# tm-duplicator.net
KiCad netlist of a schematic drawn in EasyEDA
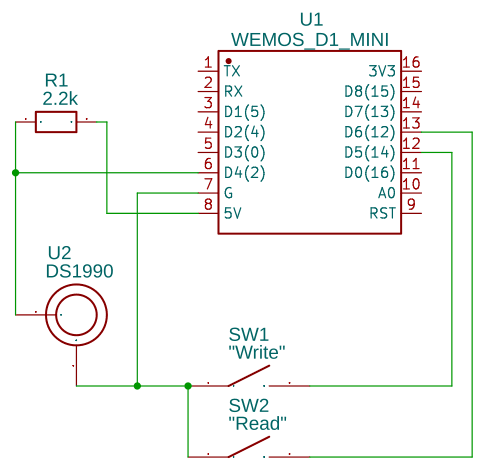
[diagram p0: schematic sheet]

(export (version "E")
  (design (tool "Eeschema 10.0.6"))
  (components
    (comp (ref "R1") (value "2.2k") (libsource (lib "") (part "R_0603_EU")))
    (comp (ref "SW1")
      (value "\"Write\"")
      (fields (field (name "BOM_Manufacturer Part") "Button"))
      (libsource (lib "") (part "PUSH BTM"))
    )
    (comp (ref "SW2")
      (value "\"Read\"")
      (fields (field (name "BOM_Manufacturer Part") "Button"))
      (libsource (lib "") (part "PUSH BTM"))
    )
    (comp (ref "U1")
      (value "WEMOS_D1_MINI")
      (fields
        (field (name "BOM_Manufacturer Part") "Wemos_D1_mini_Pro4")
        (field (name "BOM_Supplier Part") "C2837266")
      )
      (libsource (lib "") (part "WEMOS_D1_MINI_PRO4"))
    )
    (comp (ref "U2") (value "DS1990") (libsource (lib "") (part "DS1990")))
  )
  (nets
    (net (code "1") (name "Net-(U1-5V)") (class "Default")
      (node (ref "R1") (pin "2") (pinfunction "2_2") (pintype "unspecified"))
      (node (ref "U1") (pin "8") (pinfunction "5V_8") (pintype "unspecified"))
    )
    (net (code "2") (name "Net-(U1-D4(2))") (class "Default")
      (node (ref "R1") (pin "1") (pinfunction "1_1") (pintype "unspecified"))
      (node (ref "U1") (pin "6") (pinfunction "D4(2)_6") (pintype "unspecified"))
      (node (ref "U2") (pin "1") (pinfunction "1_1") (pintype "unspecified"))
    )
    (net (code "3") (name "Net-(U1-D5(14))") (class "Default")
      (node (ref "SW1") (pin "2") (pinfunction "2_2") (pintype "unspecified"))
      (node (ref "U1") (pin "12") (pinfunction "D5(14)_12") (pintype "unspecified"))
    )
    (net (code "4") (name "Net-(U1-D6(12))") (class "Default")
      (node (ref "SW2") (pin "2") (pinfunction "2_2") (pintype "unspecified"))
      (node (ref "U1") (pin "13") (pinfunction "D6(12)_13") (pintype "unspecified"))
    )
    (net (code "5") (name "Net-(U1-G)") (class "Default")
      (node (ref "SW1") (pin "1") (pinfunction "1_1") (pintype "unspecified"))
      (node (ref "SW2") (pin "1") (pinfunction "1_1") (pintype "unspecified"))
      (node (ref "U1") (pin "7") (pinfunction "G_7") (pintype "unspecified"))
      (node (ref "U2") (pin "2") (pinfunction "2_2") (pintype "unspecified"))
    )
    (net (code "6") (name "unconnected-(U1-3V3-Pad16)") (class "Default")
      (node (ref "U1") (pin "16") (pinfunction "3V3_16") (pintype "unspecified"))
    )
    (net (code "7") (name "unconnected-(U1-A0-Pad10)") (class "Default")
      (node (ref "U1") (pin "10") (pinfunction "A0_10") (pintype "unspecified"))
    )
    (net (code "8") (name "unconnected-(U1-D0(16)-Pad11)") (class "Default")
      (node (ref "U1") (pin "11") (pinfunction "D0(16)_11") (pintype "unspecified"))
    )
    (net (code "9") (name "unconnected-(U1-D1(5)-Pad3)") (class "Default")
      (node (ref "U1") (pin "3") (pinfunction "D1(5)_3") (pintype "unspecified"))
    )
    (net (code "10") (name "unconnected-(U1-D2(4)-Pad4)") (class "Default")
      (node (ref "U1") (pin "4") (pinfunction "D2(4)_4") (pintype "unspecified"))
    )
    (net (code "11") (name "unconnected-(U1-D3(0)-Pad5)") (class "Default")
      (node (ref "U1") (pin "5") (pinfunction "D3(0)_5") (pintype "unspecified"))
    )
    (net (code "12") (name "unconnected-(U1-D7(13)-Pad14)") (class "Default")
      (node (ref "U1") (pin "14") (pinfunction "D7(13)_14") (pintype "unspecified"))
    )
    (net (code "13") (name "unconnected-(U1-D8(15)-Pad15)") (class "Default")
      (node (ref "U1") (pin "15") (pinfunction "D8(15)_15") (pintype "unspecified"))
    )
    (net (code "14") (name "unconnected-(U1-RST-Pad9)") (class "Default")
      (node (ref "U1") (pin "9") (pinfunction "RST_9") (pintype "unspecified"))
    )
    (net (code "15") (name "unconnected-(U1-RX-Pad2)") (class "Default")
      (node (ref "U1") (pin "2") (pinfunction "RX_2") (pintype "unspecified"))
    )
    (net (code "16") (name "unconnected-(U1-TX-Pad1)") (class "Default")
      (node (ref "U1") (pin "1") (pinfunction "TX_1") (pintype "unspecified"))
    )
  )
)
